# IO.net
KiCad netlist of a schematic drawn in Altium Designer
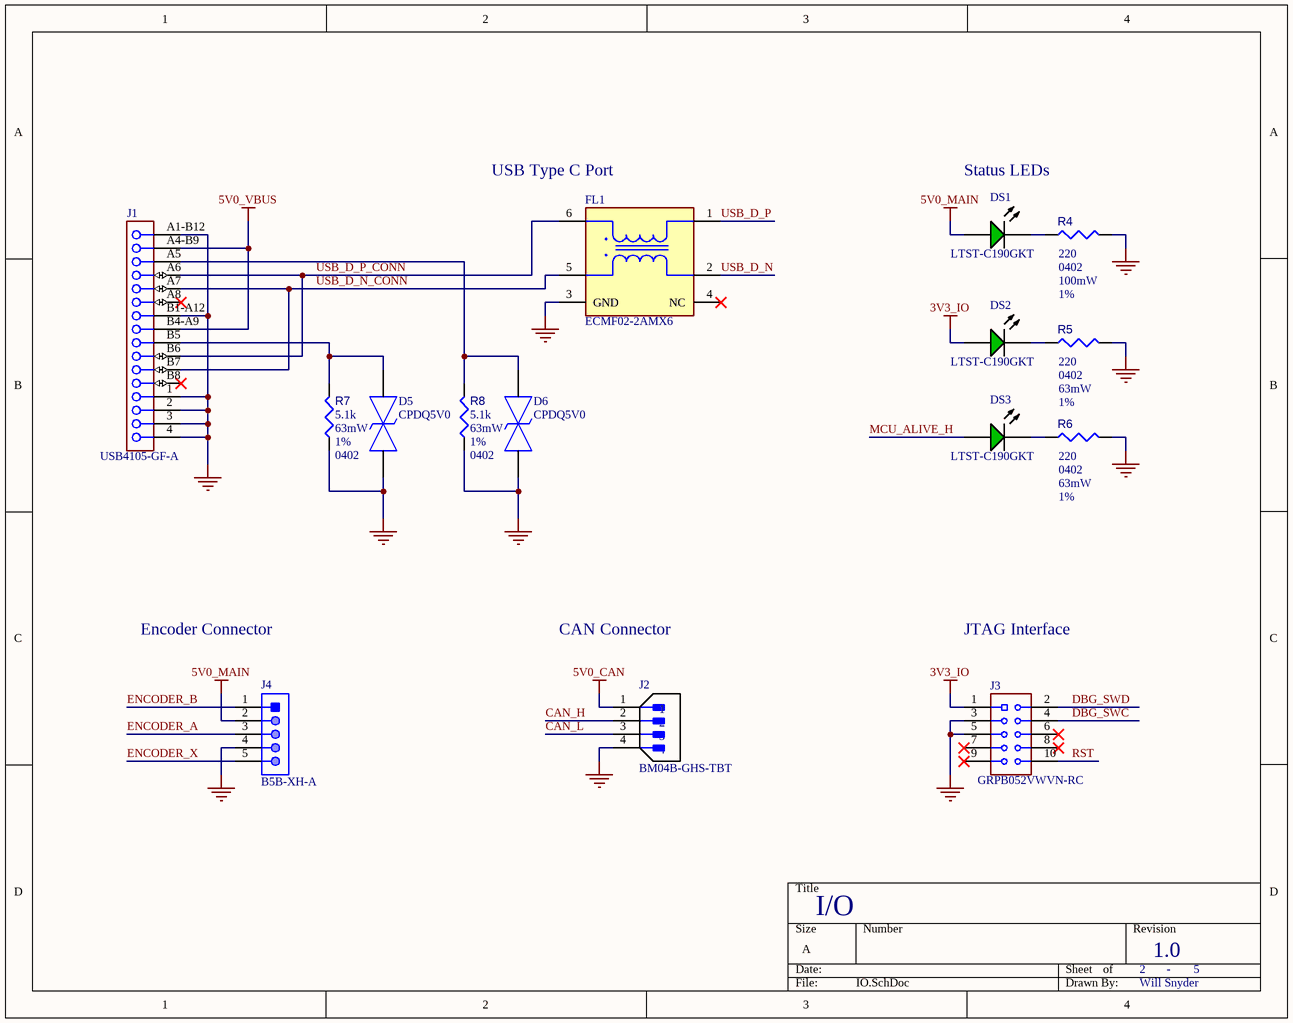
[diagram p0: IO.SchDoc]

(export (version "E")
  (design (tool "Eeschema 10.0.6"))
  (components
    (comp (ref "D5")
      (value "CPDQ5V0")
      (footprint "MBTB-D-SOD-923F-IMP-0402")
      (description "18.6V Clamp 9.4A (8/20Âµs) Ipp Tvs Diode Surface Mount 0402/SOD-923F")
      (fields (field (name "MF") "Comchip Technology") (field (name "MP") "CPDQ5V0-HF"))
      (libsource (lib "Personal Workspace") (part "CPDQ5V0-HF"))
    )
    (comp (ref "D6")
      (value "CPDQ5V0")
      (footprint "MBTB-D-SOD-923F-IMP-0402")
      (description "18.6V Clamp 9.4A (8/20Âµs) Ipp Tvs Diode Surface Mount 0402/SOD-923F")
      (fields (field (name "MF") "Comchip Technology") (field (name "MP") "CPDQ5V0-HF"))
      (libsource (lib "Personal Workspace") (part "CPDQ5V0-HF"))
    )
    (comp (ref "DS1")
      (value "LTST-C190GKT")
      (footprint "LTST-C190GKT_V")
      (description "LED Uni-Color Green, 100 mW, 30 mA, -55 to 85 degC, 2-Pin SMD, RoHS, Tape and Reel")
      (fields (field (name "POWER") "100mW") (field (name "MANUFACTURER") "Lite-On"))
      (libsource (lib "Personal Workspace") (part "LED-GREEN-AK-2"))
    )
    (comp (ref "DS2")
      (value "LTST-C190GKT")
      (footprint "LTST-C190GKT_V")
      (description "LED Uni-Color Green, 100 mW, 30 mA, -55 to 85 degC, 2-Pin SMD, RoHS, Tape and Reel")
      (fields (field (name "POWER") "100mW") (field (name "MANUFACTURER") "Lite-On"))
      (libsource (lib "Personal Workspace") (part "LED-GREEN-AK-2"))
    )
    (comp (ref "DS3")
      (value "LTST-C190GKT")
      (footprint "LTST-C190GKT_V")
      (description "LED Uni-Color Green, 100 mW, 30 mA, -55 to 85 degC, 2-Pin SMD, RoHS, Tape and Reel")
      (fields (field (name "POWER") "100mW") (field (name "MANUFACTURER") "Lite-On"))
      (libsource (lib "Personal Workspace") (part "LED-GREEN-AK-2"))
    )
    (comp (ref "FL1")
      (value "ECMF02-2AMX6")
      (footprint "FP-QFN-6L-IPC_A")
      (description "Data Line Filter, 2 Function(s), 6 Pin(s), Plastic")
      (libsource (lib "Personal Workspace") (part "8feffc7f24acfb857157da90e949b57"))
    )
    (comp (ref "J1")
      (value "USB4105-GF-A")
      (footprint "FP-USB4105-GF-A-MFG")
      (description "Conn USB 2.0 Type C RCP 24 POS 0.3mm/0.5mm Solder RA SMD 24 Terminal 1 Port T/R")
      (libsource (lib "Personal Workspace") (part "USB4105-GF-A"))
    )
    (comp (ref "J2")
      (value "BM04B-GHS-TBT")
      (footprint "FP-BM04B-GHS-TBT_LF_SN-MFG")
      (description "Conn Shrouded Header HDR 4 POS 1.25mm Solder ST Top Entry SMD T/R")
      (libsource (lib "Personal Workspace") (part "BM04B-GHS-TBT"))
    )
    (comp (ref "J3")
      (value "GRPB052VWVN-RC")
      (footprint "SULLINS_GRPB052VWVN-RC")
      (description "Connector Header Through Hole 10 position 0.050 (1.27mm)")
      (fields (field (name "MF") "Sullins"))
      (libsource (lib "Personal Workspace") (part "GRPB052VWVN-RC"))
    )
    (comp (ref "J4")
      (value "B5B-XH-A")
      (footprint "JST_B5B-XH-A")
      (description "Connector Header, XH Series, 5 Position, 2.50mm, Through Hole, Press-Fit, Solder, Natural")
      (libsource (lib "Personal Workspace") (part "B5B-XH-AM(LF)(SN)"))
    )
    (comp (ref "R4")
      (value "220")
      (footprint "RESC1005X40X25NL05T05")
      (fields
        (field (name "CASE/PACKAGE") "0402")
        (field (name "TOLERANCE") "1%")
        (field (name "POWER") "100mW")
        (field (name "Comment") "ERJ-2RKF1430X")
      )
      (libsource (lib "Personal Workspace") (part "RES-2"))
    )
    (comp (ref "R5")
      (value "220")
      (footprint "RESC1005X40X25NL05T05")
      (fields
        (field (name "TOLERANCE") "1%")
        (field (name "POWER") "63mW")
        (field (name "CASE/PACKAGE") "0402")
        (field (name "Comment") "CRCW040259R0FKED")
      )
      (libsource (lib "Personal Workspace") (part "RES-2"))
    )
    (comp (ref "R6")
      (value "220")
      (footprint "RESC1005X40X25NL05T05")
      (fields
        (field (name "TOLERANCE") "1%")
        (field (name "POWER") "63mW")
        (field (name "CASE/PACKAGE") "0402")
        (field (name "Comment") "CRCW040259R0FKED")
      )
      (libsource (lib "Personal Workspace") (part "RES-2"))
    )
    (comp (ref "R7")
      (value "5.1k")
      (footprint "RESC1005X40X25NL05T05")
      (description "Fixed Resistor, Thin Film, 0.063W, 5100ohm, 50V, 1% +/-Tol, 50ppm/Cel, Surface Mount, 0402")
      (fields
        (field (name "POWER") "63mW")
        (field (name "TOLERANCE") "1%")
        (field (name "CASE/PACKAGE") "0402")
        (field (name "Comment") "MCS04020C5101FE000")
      )
      (libsource (lib "Personal Workspace") (part "RES-2"))
    )
    (comp (ref "R8")
      (value "5.1k")
      (footprint "RESC1005X40X25NL05T05")
      (description "Fixed Resistor, Thin Film, 0.063W, 5100ohm, 50V, 1% +/-Tol, 50ppm/Cel, Surface Mount, 0402")
      (fields
        (field (name "POWER") "63mW")
        (field (name "TOLERANCE") "1%")
        (field (name "CASE/PACKAGE") "0402")
        (field (name "Comment") "MCS04020C5101FE000")
      )
      (libsource (lib "Personal Workspace") (part "RES-2"))
    )
  )
  (nets
    (net (code "1") (name "/CAN_H") (class "Default")
      (node (ref "J2") (pin "2") (pinfunction "2_2") (pintype "passive"))
    )
    (net (code "2") (name "/CAN_L") (class "Default")
      (node (ref "J2") (pin "3") (pinfunction "3_3") (pintype "passive"))
    )
    (net (code "3") (name "/DBG_SWC") (class "Default")
      (node (ref "J3") (pin "4") (pinfunction "4_4") (pintype "passive"))
    )
    (net (code "4") (name "/DBG_SWD") (class "Default")
      (node (ref "J3") (pin "2") (pinfunction "2_2") (pintype "passive"))
    )
    (net (code "5") (name "/ENCODER_A") (class "Default")
      (node (ref "J4") (pin "3") (pinfunction "3_3") (pintype "passive"))
    )
    (net (code "6") (name "/ENCODER_B") (class "Default")
      (node (ref "J4") (pin "1") (pinfunction "1_1") (pintype "passive"))
    )
    (net (code "7") (name "/ENCODER_X") (class "Default")
      (node (ref "J4") (pin "5") (pinfunction "5_5") (pintype "passive"))
    )
    (net (code "8") (name "/MCU_ALIVE_H") (class "Default")
      (node (ref "DS3") (pin "1") (pinfunction "A_1") (pintype "passive"))
    )
    (net (code "9") (name "/RST") (class "Default")
      (node (ref "J3") (pin "10") (pinfunction "10_10") (pintype "passive"))
    )
    (net (code "10") (name "/USB_D_N") (class "Default")
      (node (ref "FL1") (pin "2") (pinfunction "D-_2") (pintype "passive"))
    )
    (net (code "11") (name "/USB_D_N_CONN") (class "Default")
      (node (ref "FL1") (pin "5") (pinfunction "D-_5") (pintype "passive"))
      (node (ref "J1") (pin "A7") (pinfunction "Dn1_A7") (pintype "bidirectional"))
      (node (ref "J1") (pin "B7") (pinfunction "Dn2_B7") (pintype "bidirectional"))
    )
    (net (code "12") (name "/USB_D_P") (class "Default")
      (node (ref "FL1") (pin "1") (pinfunction "D+_1") (pintype "passive"))
    )
    (net (code "13") (name "/USB_D_P_CONN") (class "Default")
      (node (ref "FL1") (pin "6") (pinfunction "D+_6") (pintype "passive"))
      (node (ref "J1") (pin "A6") (pinfunction "Dp1_A6") (pintype "bidirectional"))
      (node (ref "J1") (pin "B6") (pinfunction "Dp2_B6") (pintype "bidirectional"))
    )
    (net (code "14") (name "3V3_IO") (class "Default")
      (node (ref "DS2") (pin "1") (pinfunction "A_1") (pintype "passive"))
      (node (ref "J3") (pin "1") (pinfunction "1_1") (pintype "passive"))
    )
    (net (code "15") (name "5V0_CAN") (class "Default")
      (node (ref "J2") (pin "1") (pinfunction "1_1") (pintype "passive"))
    )
    (net (code "16") (name "5V0_MAIN") (class "Default")
      (node (ref "DS1") (pin "1") (pinfunction "A_1") (pintype "passive"))
      (node (ref "J4") (pin "2") (pinfunction "2_2") (pintype "passive"))
    )
    (net (code "17") (name "5V0_VBUS") (class "Default")
      (node (ref "J1") (pin "A4-B9") (pinfunction "VBUS_A4-B9") (pintype "power_in"))
      (node (ref "J1") (pin "B4-A9") (pinfunction "VBUS_B4-A9") (pintype "power_in"))
    )
    (net (code "18") (name "GND") (class "Default")
      (node (ref "D5") (pin "2") (pinfunction "A_2") (pintype "passive"))
      (node (ref "D6") (pin "2") (pinfunction "A_2") (pintype "passive"))
      (node (ref "FL1") (pin "3") (pinfunction "GND_3") (pintype "power_in"))
      (node (ref "J1") (pin "1") (pinfunction "MNT_1_1") (pintype "power_in"))
      (node (ref "J1") (pin "2") (pinfunction "MNT_2_2") (pintype "power_in"))
      (node (ref "J1") (pin "3") (pinfunction "MNT_3_3") (pintype "power_in"))
      (node (ref "J1") (pin "4") (pinfunction "MNT_4_4") (pintype "power_in"))
      (node (ref "J1") (pin "A1-B12") (pinfunction "GND_A1-B12") (pintype "power_in"))
      (node (ref "J1") (pin "B1-A12") (pinfunction "GND_B1-A12") (pintype "power_in"))
      (node (ref "J2") (pin "4") (pinfunction "4_4") (pintype "passive"))
      (node (ref "J3") (pin "3") (pinfunction "3_3") (pintype "passive"))
      (node (ref "J3") (pin "5") (pinfunction "5_5") (pintype "passive"))
      (node (ref "J4") (pin "4") (pinfunction "4_4") (pintype "passive"))
      (node (ref "R4") (pin "2") (pinfunction "2_2") (pintype "passive"))
      (node (ref "R5") (pin "2") (pinfunction "2_2") (pintype "passive"))
      (node (ref "R6") (pin "2") (pinfunction "2_2") (pintype "passive"))
      (node (ref "R7") (pin "2") (pinfunction "2_2") (pintype "passive"))
      (node (ref "R8") (pin "2") (pinfunction "2_2") (pintype "passive"))
    )
    (net (code "19") (name "Net-(D5-K)") (class "Default")
      (node (ref "D5") (pin "1") (pinfunction "K_1") (pintype "passive"))
      (node (ref "J1") (pin "B5") (pinfunction "CC2_B5") (pintype "passive"))
      (node (ref "R7") (pin "1") (pinfunction "1_1") (pintype "passive"))
    )
    (net (code "20") (name "Net-(D6-K)") (class "Default")
      (node (ref "D6") (pin "1") (pinfunction "K_1") (pintype "passive"))
      (node (ref "J1") (pin "A5") (pinfunction "CC1_A5") (pintype "passive"))
      (node (ref "R8") (pin "1") (pinfunction "1_1") (pintype "passive"))
    )
    (net (code "21") (name "Net-(DS1-K)") (class "Default")
      (node (ref "DS1") (pin "2") (pinfunction "K_2") (pintype "passive"))
      (node (ref "R4") (pin "1") (pinfunction "1_1") (pintype "passive"))
    )
    (net (code "22") (name "Net-(DS2-K)") (class "Default")
      (node (ref "DS2") (pin "2") (pinfunction "K_2") (pintype "passive"))
      (node (ref "R5") (pin "1") (pinfunction "1_1") (pintype "passive"))
    )
    (net (code "23") (name "Net-(DS3-K)") (class "Default")
      (node (ref "DS3") (pin "2") (pinfunction "K_2") (pintype "passive"))
      (node (ref "R6") (pin "1") (pinfunction "1_1") (pintype "passive"))
    )
    (net (code "24") (name "unconnected-(FL1-NC-Pad4)") (class "Default")
      (node (ref "FL1") (pin "4") (pinfunction "NC_4") (pintype "passive+no_connect"))
    )
    (net (code "25") (name "unconnected-(J1-SBU1-PadA8)") (class "Default")
      (node (ref "J1") (pin "A8") (pinfunction "SBU1_A8") (pintype "bidirectional+no_connect"))
    )
    (net (code "26") (name "unconnected-(J1-SBU2-PadB8)") (class "Default")
      (node (ref "J1") (pin "B8") (pinfunction "SBU2_B8") (pintype "bidirectional+no_connect"))
    )
    (net (code "27") (name "unconnected-(J3-Pad6)") (class "Default")
      (node (ref "J3") (pin "6") (pinfunction "6_6") (pintype "passive+no_connect"))
    )
    (net (code "28") (name "unconnected-(J3-Pad7)") (class "Default")
      (node (ref "J3") (pin "7") (pinfunction "7_7") (pintype "passive+no_connect"))
    )
    (net (code "29") (name "unconnected-(J3-Pad8)") (class "Default")
      (node (ref "J3") (pin "8") (pinfunction "8_8") (pintype "passive+no_connect"))
    )
    (net (code "30") (name "unconnected-(J3-Pad9)") (class "Default")
      (node (ref "J3") (pin "9") (pinfunction "9_9") (pintype "passive+no_connect"))
    )
  )
)
